# HQspd_board.net
KiCad netlist of a schematic drawn in EAGLE
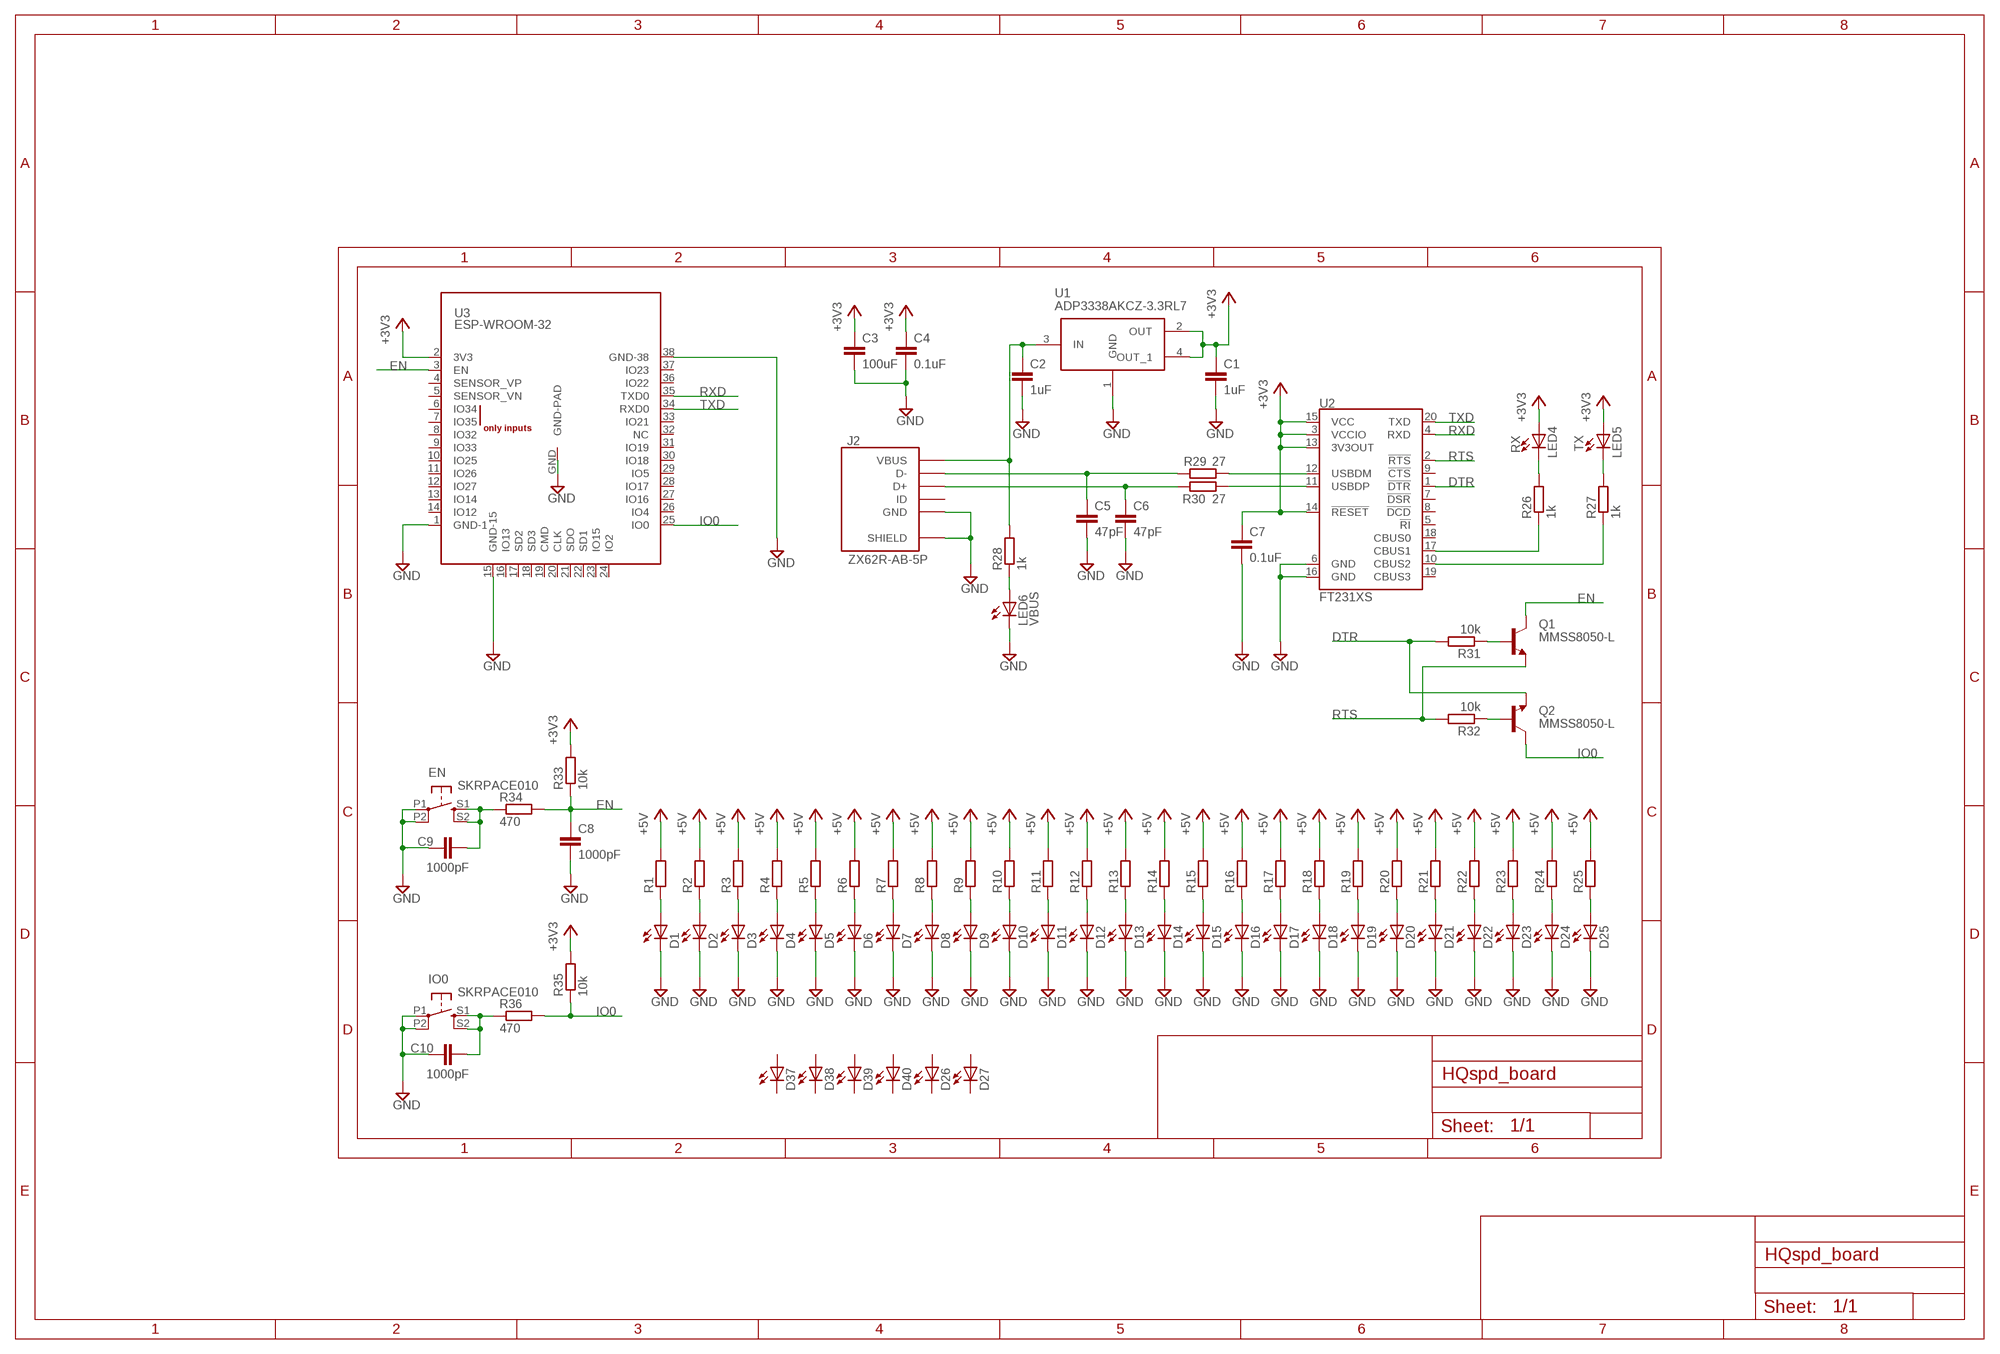
[diagram p0: schematic, sheet 1]

(export (version "E")
  (design (tool "Eeschema 10.0.6"))
  (components
    (comp (ref "C1")
      (value "1uF")
      (footprint "eagle-import:C0603")
      (libsource (lib "eagle-import") (part "C-EUC0603"))
    )
    (comp (ref "C2")
      (value "1uF")
      (footprint "eagle-import:C0603")
      (libsource (lib "eagle-import") (part "C-EUC0603"))
    )
    (comp (ref "C3")
      (value "100uF")
      (footprint "eagle-import:C1210")
      (libsource (lib "eagle-import") (part "C-EUC1210"))
    )
    (comp (ref "C4")
      (value "0.1uF")
      (footprint "eagle-import:C0603")
      (libsource (lib "eagle-import") (part "C-EUC0603"))
    )
    (comp (ref "C5")
      (value "47pF")
      (footprint "eagle-import:C0603")
      (libsource (lib "eagle-import") (part "C-EUC0603"))
    )
    (comp (ref "C6")
      (value "47pF")
      (footprint "eagle-import:C0603")
      (libsource (lib "eagle-import") (part "C-EUC0603"))
    )
    (comp (ref "C7")
      (value "0.1uF")
      (footprint "eagle-import:C0603")
      (libsource (lib "eagle-import") (part "C-EUC0603"))
    )
    (comp (ref "C8")
      (value "1000pF")
      (footprint "eagle-import:C0603")
      (libsource (lib "eagle-import") (part "C-EUC0603"))
    )
    (comp (ref "C9")
      (value "1000pF")
      (footprint "eagle-import:C0603")
      (libsource (lib "eagle-import") (part "C-EUC0603"))
    )
    (comp (ref "C10")
      (value "1000pF")
      (footprint "eagle-import:C0603")
      (libsource (lib "eagle-import") (part "C-EUC0603"))
    )
    (comp (ref "D1")
      (value "LEDCHIPLED_0603")
      (footprint "eagle-import:CHIPLED_0603")
      (libsource (lib "eagle-import") (part "LEDCHIPLED_0603"))
    )
    (comp (ref "D2")
      (value "LEDCHIPLED_0603")
      (footprint "eagle-import:CHIPLED_0603")
      (libsource (lib "eagle-import") (part "LEDCHIPLED_0603"))
    )
    (comp (ref "D3")
      (value "LEDCHIPLED_0603")
      (footprint "eagle-import:CHIPLED_0603")
      (libsource (lib "eagle-import") (part "LEDCHIPLED_0603"))
    )
    (comp (ref "D4")
      (value "LEDCHIPLED_0603")
      (footprint "eagle-import:CHIPLED_0603")
      (libsource (lib "eagle-import") (part "LEDCHIPLED_0603"))
    )
    (comp (ref "D5")
      (value "LEDCHIPLED_0603")
      (footprint "eagle-import:CHIPLED_0603")
      (libsource (lib "eagle-import") (part "LEDCHIPLED_0603"))
    )
    (comp (ref "D6")
      (value "LEDCHIPLED_0603")
      (footprint "eagle-import:CHIPLED_0603")
      (libsource (lib "eagle-import") (part "LEDCHIPLED_0603"))
    )
    (comp (ref "D7")
      (value "LEDCHIPLED_0603")
      (footprint "eagle-import:CHIPLED_0603")
      (libsource (lib "eagle-import") (part "LEDCHIPLED_0603"))
    )
    (comp (ref "D8")
      (value "LEDCHIPLED_0603")
      (footprint "eagle-import:CHIPLED_0603")
      (libsource (lib "eagle-import") (part "LEDCHIPLED_0603"))
    )
    (comp (ref "D9")
      (value "LEDCHIPLED_0603")
      (footprint "eagle-import:CHIPLED_0603")
      (libsource (lib "eagle-import") (part "LEDCHIPLED_0603"))
    )
    (comp (ref "D10")
      (value "LEDCHIPLED_0603")
      (footprint "eagle-import:CHIPLED_0603")
      (libsource (lib "eagle-import") (part "LEDCHIPLED_0603"))
    )
    (comp (ref "D11")
      (value "LEDCHIPLED_0603")
      (footprint "eagle-import:CHIPLED_0603")
      (libsource (lib "eagle-import") (part "LEDCHIPLED_0603"))
    )
    (comp (ref "D12")
      (value "LEDCHIPLED_0603")
      (footprint "eagle-import:CHIPLED_0603")
      (libsource (lib "eagle-import") (part "LEDCHIPLED_0603"))
    )
    (comp (ref "D13")
      (value "LEDCHIPLED_0603")
      (footprint "eagle-import:CHIPLED_0603")
      (libsource (lib "eagle-import") (part "LEDCHIPLED_0603"))
    )
    (comp (ref "D14")
      (value "LEDCHIPLED_0603")
      (footprint "eagle-import:CHIPLED_0603")
      (libsource (lib "eagle-import") (part "LEDCHIPLED_0603"))
    )
    (comp (ref "D15")
      (value "LEDCHIPLED_0603")
      (footprint "eagle-import:CHIPLED_0603")
      (libsource (lib "eagle-import") (part "LEDCHIPLED_0603"))
    )
    (comp (ref "D16")
      (value "LEDCHIPLED_0603")
      (footprint "eagle-import:CHIPLED_0603")
      (libsource (lib "eagle-import") (part "LEDCHIPLED_0603"))
    )
    (comp (ref "D17")
      (value "LEDCHIPLED_0603")
      (footprint "eagle-import:CHIPLED_0603")
      (libsource (lib "eagle-import") (part "LEDCHIPLED_0603"))
    )
    (comp (ref "D18")
      (value "LEDCHIPLED_0603")
      (footprint "eagle-import:CHIPLED_0603")
      (libsource (lib "eagle-import") (part "LEDCHIPLED_0603"))
    )
    (comp (ref "D19")
      (value "LEDCHIPLED_0603")
      (footprint "eagle-import:CHIPLED_0603")
      (libsource (lib "eagle-import") (part "LEDCHIPLED_0603"))
    )
    (comp (ref "D20")
      (value "LEDCHIPLED_0603")
      (footprint "eagle-import:CHIPLED_0603")
      (libsource (lib "eagle-import") (part "LEDCHIPLED_0603"))
    )
    (comp (ref "D21")
      (value "LEDCHIPLED_0603")
      (footprint "eagle-import:CHIPLED_0603")
      (libsource (lib "eagle-import") (part "LEDCHIPLED_0603"))
    )
    (comp (ref "D22")
      (value "LEDCHIPLED_0603")
      (footprint "eagle-import:CHIPLED_0603")
      (libsource (lib "eagle-import") (part "LEDCHIPLED_0603"))
    )
    (comp (ref "D23")
      (value "LEDCHIPLED_0603")
      (footprint "eagle-import:CHIPLED_0603")
      (libsource (lib "eagle-import") (part "LEDCHIPLED_0603"))
    )
    (comp (ref "D24")
      (value "LEDCHIPLED_0603")
      (footprint "eagle-import:CHIPLED_0603")
      (libsource (lib "eagle-import") (part "LEDCHIPLED_0603"))
    )
    (comp (ref "D25")
      (value "LEDCHIPLED_0603")
      (footprint "eagle-import:CHIPLED_0603")
      (libsource (lib "eagle-import") (part "LEDCHIPLED_0603"))
    )
    (comp (ref "D26")
      (value "LED3MM")
      (footprint "eagle-import:LED3MM")
      (libsource (lib "eagle-import") (part "LED3MM"))
    )
    (comp (ref "D27")
      (value "LED3MM")
      (footprint "eagle-import:LED3MM")
      (libsource (lib "eagle-import") (part "LED3MM"))
    )
    (comp (ref "D37")
      (value "LED3MM")
      (footprint "eagle-import:LED3MM")
      (libsource (lib "eagle-import") (part "LED3MM"))
    )
    (comp (ref "D38")
      (value "LED3MM")
      (footprint "eagle-import:LED3MM")
      (libsource (lib "eagle-import") (part "LED3MM"))
    )
    (comp (ref "D39")
      (value "LED3MM")
      (footprint "eagle-import:LED3MM")
      (libsource (lib "eagle-import") (part "LED3MM"))
    )
    (comp (ref "D40")
      (value "LED3MM")
      (footprint "eagle-import:LED3MM")
      (libsource (lib "eagle-import") (part "LED3MM"))
    )
    (comp (ref "EN")
      (value "SKRPACE010")
      (footprint "eagle-import:SKRPACE010")
      (libsource (lib "eagle-import") (part "SKRPACE010"))
    )
    (comp (ref "IO0")
      (value "SKRPACE010")
      (footprint "eagle-import:SKRPACE010")
      (libsource (lib "eagle-import") (part "SKRPACE010"))
    )
    (comp (ref "J2")
      (value "ZX62R-AB-5P")
      (footprint "eagle-import:ZX62R-B-5PA")
      (libsource (lib "eagle-import") (part "ZX62R-AB-5P"))
    )
    (comp (ref "LED4")
      (value "RX")
      (footprint "eagle-import:CHIPLED_0603")
      (libsource (lib "eagle-import") (part "LEDCHIPLED_0603"))
    )
    (comp (ref "LED5")
      (value "TX")
      (footprint "eagle-import:CHIPLED_0603")
      (libsource (lib "eagle-import") (part "LEDCHIPLED_0603"))
    )
    (comp (ref "LED6")
      (value "VBUS")
      (footprint "eagle-import:CHIPLED_0603")
      (libsource (lib "eagle-import") (part "LEDCHIPLED_0603"))
    )
    (comp (ref "Q1")
      (value "MMSS8050-L")
      (footprint "eagle-import:SOT23")
      (libsource (lib "eagle-import") (part "MMSS8050-L"))
    )
    (comp (ref "Q2")
      (value "MMSS8050-L")
      (footprint "eagle-import:SOT23")
      (libsource (lib "eagle-import") (part "MMSS8050-L"))
    )
    (comp (ref "R1")
      (value "R-EU_R0603")
      (footprint "eagle-import:R0603")
      (libsource (lib "eagle-import") (part "R-EU_R0603"))
    )
    (comp (ref "R2")
      (value "R-EU_R0603")
      (footprint "eagle-import:R0603")
      (libsource (lib "eagle-import") (part "R-EU_R0603"))
    )
    (comp (ref "R3")
      (value "R-EU_R0603")
      (footprint "eagle-import:R0603")
      (libsource (lib "eagle-import") (part "R-EU_R0603"))
    )
    (comp (ref "R4")
      (value "R-EU_R0603")
      (footprint "eagle-import:R0603")
      (libsource (lib "eagle-import") (part "R-EU_R0603"))
    )
    (comp (ref "R5")
      (value "R-EU_R0603")
      (footprint "eagle-import:R0603")
      (libsource (lib "eagle-import") (part "R-EU_R0603"))
    )
    (comp (ref "R6")
      (value "R-EU_R0603")
      (footprint "eagle-import:R0603")
      (libsource (lib "eagle-import") (part "R-EU_R0603"))
    )
    (comp (ref "R7")
      (value "R-EU_R0603")
      (footprint "eagle-import:R0603")
      (libsource (lib "eagle-import") (part "R-EU_R0603"))
    )
    (comp (ref "R8")
      (value "R-EU_R0603")
      (footprint "eagle-import:R0603")
      (libsource (lib "eagle-import") (part "R-EU_R0603"))
    )
    (comp (ref "R9")
      (value "R-EU_R0603")
      (footprint "eagle-import:R0603")
      (libsource (lib "eagle-import") (part "R-EU_R0603"))
    )
    (comp (ref "R10")
      (value "R-EU_R0603")
      (footprint "eagle-import:R0603")
      (libsource (lib "eagle-import") (part "R-EU_R0603"))
    )
    (comp (ref "R11")
      (value "R-EU_R0603")
      (footprint "eagle-import:R0603")
      (libsource (lib "eagle-import") (part "R-EU_R0603"))
    )
    (comp (ref "R12")
      (value "R-EU_R0603")
      (footprint "eagle-import:R0603")
      (libsource (lib "eagle-import") (part "R-EU_R0603"))
    )
    (comp (ref "R13")
      (value "R-EU_R0603")
      (footprint "eagle-import:R0603")
      (libsource (lib "eagle-import") (part "R-EU_R0603"))
    )
    (comp (ref "R14")
      (value "R-EU_R0603")
      (footprint "eagle-import:R0603")
      (libsource (lib "eagle-import") (part "R-EU_R0603"))
    )
    (comp (ref "R15")
      (value "R-EU_R0603")
      (footprint "eagle-import:R0603")
      (libsource (lib "eagle-import") (part "R-EU_R0603"))
    )
    (comp (ref "R16")
      (value "R-EU_R0603")
      (footprint "eagle-import:R0603")
      (libsource (lib "eagle-import") (part "R-EU_R0603"))
    )
    (comp (ref "R17")
      (value "R-EU_R0603")
      (footprint "eagle-import:R0603")
      (libsource (lib "eagle-import") (part "R-EU_R0603"))
    )
    (comp (ref "R18")
      (value "R-EU_R0603")
      (footprint "eagle-import:R0603")
      (libsource (lib "eagle-import") (part "R-EU_R0603"))
    )
    (comp (ref "R19")
      (value "R-EU_R0603")
      (footprint "eagle-import:R0603")
      (libsource (lib "eagle-import") (part "R-EU_R0603"))
    )
    (comp (ref "R20")
      (value "R-EU_R0603")
      (footprint "eagle-import:R0603")
      (libsource (lib "eagle-import") (part "R-EU_R0603"))
    )
    (comp (ref "R21")
      (value "R-EU_R0603")
      (footprint "eagle-import:R0603")
      (libsource (lib "eagle-import") (part "R-EU_R0603"))
    )
    (comp (ref "R22")
      (value "R-EU_R0603")
      (footprint "eagle-import:R0603")
      (libsource (lib "eagle-import") (part "R-EU_R0603"))
    )
    (comp (ref "R23")
      (value "R-EU_R0603")
      (footprint "eagle-import:R0603")
      (libsource (lib "eagle-import") (part "R-EU_R0603"))
    )
    (comp (ref "R24")
      (value "R-EU_R0603")
      (footprint "eagle-import:R0603")
      (libsource (lib "eagle-import") (part "R-EU_R0603"))
    )
    (comp (ref "R25")
      (value "R-EU_R0603")
      (footprint "eagle-import:R0603")
      (libsource (lib "eagle-import") (part "R-EU_R0603"))
    )
    (comp (ref "R26")
      (value "1k")
      (footprint "eagle-import:R0603")
      (libsource (lib "eagle-import") (part "R-EU_R0603"))
    )
    (comp (ref "R27")
      (value "1k")
      (footprint "eagle-import:R0603")
      (libsource (lib "eagle-import") (part "R-EU_R0603"))
    )
    (comp (ref "R28")
      (value "1k")
      (footprint "eagle-import:R0603")
      (libsource (lib "eagle-import") (part "R-EU_R0603"))
    )
    (comp (ref "R29")
      (value "27")
      (footprint "eagle-import:R0603")
      (libsource (lib "eagle-import") (part "R-EU_R0603"))
    )
    (comp (ref "R30")
      (value "27")
      (footprint "eagle-import:R0603")
      (libsource (lib "eagle-import") (part "R-EU_R0603"))
    )
    (comp (ref "R31")
      (value "10k")
      (footprint "eagle-import:R0603")
      (libsource (lib "eagle-import") (part "R-EU_R0603"))
    )
    (comp (ref "R32")
      (value "10k")
      (footprint "eagle-import:R0603")
      (libsource (lib "eagle-import") (part "R-EU_R0603"))
    )
    (comp (ref "R33")
      (value "10k")
      (footprint "eagle-import:R0603")
      (libsource (lib "eagle-import") (part "R-EU_R0603"))
    )
    (comp (ref "R34")
      (value "470")
      (footprint "eagle-import:R0603")
      (libsource (lib "eagle-import") (part "R-EU_R0603"))
    )
    (comp (ref "R35")
      (value "10k")
      (footprint "eagle-import:R0603")
      (libsource (lib "eagle-import") (part "R-EU_R0603"))
    )
    (comp (ref "R36")
      (value "470")
      (footprint "eagle-import:R0603")
      (libsource (lib "eagle-import") (part "R-EU_R0603"))
    )
    (comp (ref "U1")
      (value "ADP3338AKCZ-3.3RL7")
      (footprint "eagle-import:SOT230P700X180-4N")
      (fields (field (name "RS_PART_NUMBER") "9126350"))
      (libsource (lib "eagle-import") (part "ADP3338AKCZ-3.3RL7"))
    )
    (comp (ref "U2")
      (value "FT231XS")
      (footprint "eagle-import:SSOP20_L")
      (libsource (lib "eagle-import") (part "FT231XS"))
    )
    (comp (ref "U3")
      (value "ESP-WROOM-32")
      (footprint "eagle-import:ESP-WROOM-32")
      (libsource (lib "eagle-import") (part "ESP-WROOM-32"))
    )
  )
  (nets
    (net (code "1") (name "+3V3") (class "Default")
      (node (ref "C1") (pin "1") (pinfunction "1_1") (pintype "passive"))
      (node (ref "C3") (pin "1") (pinfunction "1_1") (pintype "passive"))
      (node (ref "C4") (pin "1") (pinfunction "1_1") (pintype "passive"))
      (node (ref "C7") (pin "1") (pinfunction "1_1") (pintype "passive"))
      (node (ref "LED4") (pin "A") (pinfunction "A_A") (pintype "passive"))
      (node (ref "LED5") (pin "A") (pinfunction "A_A") (pintype "passive"))
      (node (ref "R33") (pin "2") (pinfunction "2_2") (pintype "passive"))
      (node (ref "R35") (pin "2") (pinfunction "2_2") (pintype "passive"))
      (node (ref "U1") (pin "2") (pinfunction "OUT_2") (pintype "output"))
      (node (ref "U1") (pin "4") (pinfunction "OUT_1_4") (pintype "output"))
      (node (ref "U2") (pin "13") (pinfunction "3V3OUT_13") (pintype "bidirectional"))
      (node (ref "U2") (pin "14") (pinfunction "~{RESET}_14") (pintype "bidirectional"))
      (node (ref "U2") (pin "15") (pinfunction "VCC_15") (pintype "bidirectional"))
      (node (ref "U2") (pin "3") (pinfunction "VCCIO_3") (pintype "bidirectional"))
      (node (ref "U3") (pin "2") (pinfunction "3V3_2") (pintype "bidirectional"))
    )
    (net (code "2") (name "+5V") (class "Default")
      (node (ref "R1") (pin "2") (pinfunction "2_2") (pintype "passive"))
      (node (ref "R10") (pin "2") (pinfunction "2_2") (pintype "passive"))
      (node (ref "R11") (pin "2") (pinfunction "2_2") (pintype "passive"))
      (node (ref "R12") (pin "2") (pinfunction "2_2") (pintype "passive"))
      (node (ref "R13") (pin "2") (pinfunction "2_2") (pintype "passive"))
      (node (ref "R14") (pin "2") (pinfunction "2_2") (pintype "passive"))
      (node (ref "R15") (pin "2") (pinfunction "2_2") (pintype "passive"))
      (node (ref "R16") (pin "2") (pinfunction "2_2") (pintype "passive"))
      (node (ref "R17") (pin "2") (pinfunction "2_2") (pintype "passive"))
      (node (ref "R18") (pin "2") (pinfunction "2_2") (pintype "passive"))
      (node (ref "R19") (pin "2") (pinfunction "2_2") (pintype "passive"))
      (node (ref "R2") (pin "2") (pinfunction "2_2") (pintype "passive"))
      (node (ref "R20") (pin "2") (pinfunction "2_2") (pintype "passive"))
      (node (ref "R21") (pin "2") (pinfunction "2_2") (pintype "passive"))
      (node (ref "R22") (pin "2") (pinfunction "2_2") (pintype "passive"))
      (node (ref "R23") (pin "2") (pinfunction "2_2") (pintype "passive"))
      (node (ref "R24") (pin "2") (pinfunction "2_2") (pintype "passive"))
      (node (ref "R25") (pin "2") (pinfunction "2_2") (pintype "passive"))
      (node (ref "R3") (pin "2") (pinfunction "2_2") (pintype "passive"))
      (node (ref "R4") (pin "2") (pinfunction "2_2") (pintype "passive"))
      (node (ref "R5") (pin "2") (pinfunction "2_2") (pintype "passive"))
      (node (ref "R6") (pin "2") (pinfunction "2_2") (pintype "passive"))
      (node (ref "R7") (pin "2") (pinfunction "2_2") (pintype "passive"))
      (node (ref "R8") (pin "2") (pinfunction "2_2") (pintype "passive"))
      (node (ref "R9") (pin "2") (pinfunction "2_2") (pintype "passive"))
    )
    (net (code "3") (name "/DTR") (class "Default")
      (node (ref "Q2") (pin "E") (pinfunction "E_E") (pintype "passive"))
      (node (ref "R31") (pin "2") (pinfunction "2_2") (pintype "passive"))
      (node (ref "U2") (pin "1") (pinfunction "~{DTR}_1") (pintype "bidirectional"))
    )
    (net (code "4") (name "/EN") (class "Default")
      (node (ref "C8") (pin "1") (pinfunction "1_1") (pintype "passive"))
      (node (ref "Q1") (pin "C") (pinfunction "C_C") (pintype "passive"))
      (node (ref "R33") (pin "1") (pinfunction "1_1") (pintype "passive"))
      (node (ref "R34") (pin "2") (pinfunction "2_2") (pintype "passive"))
      (node (ref "U3") (pin "3") (pinfunction "EN_3") (pintype "bidirectional"))
    )
    (net (code "5") (name "/IO0") (class "Default")
      (node (ref "Q2") (pin "C") (pinfunction "C_C") (pintype "passive"))
      (node (ref "R35") (pin "1") (pinfunction "1_1") (pintype "passive"))
      (node (ref "R36") (pin "2") (pinfunction "2_2") (pintype "passive"))
      (node (ref "U3") (pin "25") (pinfunction "IO0_25") (pintype "bidirectional"))
    )
    (net (code "6") (name "/RTS") (class "Default")
      (node (ref "Q1") (pin "E") (pinfunction "E_E") (pintype "passive"))
      (node (ref "R32") (pin "2") (pinfunction "2_2") (pintype "passive"))
      (node (ref "U2") (pin "2") (pinfunction "~{RTS}_2") (pintype "bidirectional"))
    )
    (net (code "7") (name "/RXD") (class "Default")
      (node (ref "U2") (pin "4") (pinfunction "RXD_4") (pintype "bidirectional"))
      (node (ref "U3") (pin "35") (pinfunction "TXD0_35") (pintype "bidirectional"))
    )
    (net (code "8") (name "/TXD") (class "Default")
      (node (ref "U2") (pin "20") (pinfunction "TXD_20") (pintype "bidirectional"))
      (node (ref "U3") (pin "34") (pinfunction "RXD0_34") (pintype "bidirectional"))
    )
    (net (code "9") (name "GND") (class "Default")
      (node (ref "C1") (pin "2") (pinfunction "2_2") (pintype "passive"))
      (node (ref "C10") (pin "1") (pinfunction "1_1") (pintype "passive"))
      (node (ref "C2") (pin "2") (pinfunction "2_2") (pintype "passive"))
      (node (ref "C3") (pin "2") (pinfunction "2_2") (pintype "passive"))
      (node (ref "C4") (pin "2") (pinfunction "2_2") (pintype "passive"))
      (node (ref "C5") (pin "2") (pinfunction "2_2") (pintype "passive"))
      (node (ref "C6") (pin "2") (pinfunction "2_2") (pintype "passive"))
      (node (ref "C7") (pin "2") (pinfunction "2_2") (pintype "passive"))
      (node (ref "C8") (pin "2") (pinfunction "2_2") (pintype "passive"))
      (node (ref "C9") (pin "1") (pinfunction "1_1") (pintype "passive"))
      (node (ref "D1") (pin "C") (pinfunction "C_C") (pintype "passive"))
      (node (ref "D10") (pin "C") (pinfunction "C_C") (pintype "passive"))
      (node (ref "D11") (pin "C") (pinfunction "C_C") (pintype "passive"))
      (node (ref "D12") (pin "C") (pinfunction "C_C") (pintype "passive"))
      (node (ref "D13") (pin "C") (pinfunction "C_C") (pintype "passive"))
      (node (ref "D14") (pin "C") (pinfunction "C_C") (pintype "passive"))
      (node (ref "D15") (pin "C") (pinfunction "C_C") (pintype "passive"))
      (node (ref "D16") (pin "C") (pinfunction "C_C") (pintype "passive"))
      (node (ref "D17") (pin "C") (pinfunction "C_C") (pintype "passive"))
      (node (ref "D18") (pin "C") (pinfunction "C_C") (pintype "passive"))
      (node (ref "D19") (pin "C") (pinfunction "C_C") (pintype "passive"))
      (node (ref "D2") (pin "C") (pinfunction "C_C") (pintype "passive"))
      (node (ref "D20") (pin "C") (pinfunction "C_C") (pintype "passive"))
      (node (ref "D21") (pin "C") (pinfunction "C_C") (pintype "passive"))
      (node (ref "D22") (pin "C") (pinfunction "C_C") (pintype "passive"))
      (node (ref "D23") (pin "C") (pinfunction "C_C") (pintype "passive"))
      (node (ref "D24") (pin "C") (pinfunction "C_C") (pintype "passive"))
      (node (ref "D25") (pin "C") (pinfunction "C_C") (pintype "passive"))
      (node (ref "D3") (pin "C") (pinfunction "C_C") (pintype "passive"))
      (node (ref "D4") (pin "C") (pinfunction "C_C") (pintype "passive"))
      (node (ref "D5") (pin "C") (pinfunction "C_C") (pintype "passive"))
      (node (ref "D6") (pin "C") (pinfunction "C_C") (pintype "passive"))
      (node (ref "D7") (pin "C") (pinfunction "C_C") (pintype "passive"))
      (node (ref "D8") (pin "C") (pinfunction "C_C") (pintype "passive"))
      (node (ref "D9") (pin "C") (pinfunction "C_C") (pintype "passive"))
      (node (ref "EN") (pin "P1") (pinfunction "P_P1") (pintype "passive"))
      (node (ref "EN") (pin "P2") (pinfunction "P1_P2") (pintype "passive"))
      (node (ref "IO0") (pin "P1") (pinfunction "P_P1") (pintype "passive"))
      (node (ref "IO0") (pin "P2") (pinfunction "P1_P2") (pintype "passive"))
      (node (ref "J2") (pin "GND") (pinfunction "GND_GND") (pintype "bidirectional"))
      (node (ref "J2") (pin "SHIELD@1") (pinfunction "SHIELD_SHIELD@1") (pintype "bidirectional"))
      (node (ref "J2") (pin "SHIELD@2") (pinfunction "SHIELD_SHIELD@2") (pintype "bidirectional"))
      (node (ref "J2") (pin "SHIELD@3") (pinfunction "SHIELD_SHIELD@3") (pintype "bidirectional"))
      (node (ref "J2") (pin "SHIELD@4") (pinfunction "SHIELD_SHIELD@4") (pintype "bidirectional"))
      (node (ref "LED6") (pin "C") (pinfunction "C_C") (pintype "passive"))
      (node (ref "U1") (pin "1") (pinfunction "GND_1") (pintype "power_in"))
      (node (ref "U2") (pin "16") (pinfunction "GND_16") (pintype "bidirectional"))
      (node (ref "U2") (pin "6") (pinfunction "GND_6") (pintype "bidirectional"))
      (node (ref "U3") (pin "1") (pinfunction "GND-1_1") (pintype "bidirectional"))
      (node (ref "U3") (pin "15") (pinfunction "GND-15_15") (pintype "bidirectional"))
      (node (ref "U3") (pin "38") (pinfunction "GND-38_38") (pintype "bidirectional"))
      (node (ref "U3") (pin "GND") (pinfunction "GND-PAD_GND") (pintype "bidirectional"))
    )
    (net (code "10") (name "Net-(C5-Pad1)") (class "Default")
      (node (ref "C5") (pin "1") (pinfunction "1_1") (pintype "passive"))
      (node (ref "J2") (pin "D-") (pinfunction "D-_D-") (pintype "bidirectional"))
      (node (ref "R29") (pin "1") (pinfunction "1_1") (pintype "passive"))
    )
    (net (code "11") (name "Net-(C6-Pad1)") (class "Default")
      (node (ref "C6") (pin "1") (pinfunction "1_1") (pintype "passive"))
      (node (ref "J2") (pin "D+") (pinfunction "D+_D+") (pintype "bidirectional"))
      (node (ref "R30") (pin "1") (pinfunction "1_1") (pintype "passive"))
    )
    (net (code "12") (name "Net-(D1-PadA)") (class "Default")
      (node (ref "D1") (pin "A") (pinfunction "A_A") (pintype "passive"))
      (node (ref "R1") (pin "1") (pinfunction "1_1") (pintype "passive"))
    )
    (net (code "13") (name "Net-(D2-PadA)") (class "Default")
      (node (ref "D2") (pin "A") (pinfunction "A_A") (pintype "passive"))
      (node (ref "R2") (pin "1") (pinfunction "1_1") (pintype "passive"))
    )
    (net (code "14") (name "Net-(D3-PadA)") (class "Default")
      (node (ref "D3") (pin "A") (pinfunction "A_A") (pintype "passive"))
      (node (ref "R3") (pin "1") (pinfunction "1_1") (pintype "passive"))
    )
    (net (code "15") (name "Net-(D4-PadA)") (class "Default")
      (node (ref "D4") (pin "A") (pinfunction "A_A") (pintype "passive"))
      (node (ref "R4") (pin "1") (pinfunction "1_1") (pintype "passive"))
    )
    (net (code "16") (name "Net-(D5-PadA)") (class "Default")
      (node (ref "D5") (pin "A") (pinfunction "A_A") (pintype "passive"))
      (node (ref "R5") (pin "1") (pinfunction "1_1") (pintype "passive"))
    )
    (net (code "17") (name "Net-(D6-PadA)") (class "Default")
      (node (ref "D6") (pin "A") (pinfunction "A_A") (pintype "passive"))
      (node (ref "R6") (pin "1") (pinfunction "1_1") (pintype "passive"))
    )
    (net (code "18") (name "Net-(D7-PadA)") (class "Default")
      (node (ref "D7") (pin "A") (pinfunction "A_A") (pintype "passive"))
      (node (ref "R7") (pin "1") (pinfunction "1_1") (pintype "passive"))
    )
    (net (code "19") (name "Net-(D8-PadA)") (class "Default")
      (node (ref "D8") (pin "A") (pinfunction "A_A") (pintype "passive"))
      (node (ref "R8") (pin "1") (pinfunction "1_1") (pintype "passive"))
    )
    (net (code "20") (name "Net-(D9-PadA)") (class "Default")
      (node (ref "D9") (pin "A") (pinfunction "A_A") (pintype "passive"))
      (node (ref "R9") (pin "1") (pinfunction "1_1") (pintype "passive"))
    )
    (net (code "21") (name "Net-(D10-PadA)") (class "Default")
      (node (ref "D10") (pin "A") (pinfunction "A_A") (pintype "passive"))
      (node (ref "R10") (pin "1") (pinfunction "1_1") (pintype "passive"))
    )
    (net (code "22") (name "Net-(D11-PadA)") (class "Default")
      (node (ref "D11") (pin "A") (pinfunction "A_A") (pintype "passive"))
      (node (ref "R11") (pin "1") (pinfunction "1_1") (pintype "passive"))
    )
    (net (code "23") (name "Net-(D12-PadA)") (class "Default")
      (node (ref "D12") (pin "A") (pinfunction "A_A") (pintype "passive"))
      (node (ref "R12") (pin "1") (pinfunction "1_1") (pintype "passive"))
    )
    (net (code "24") (name "Net-(D13-PadA)") (class "Default")
      (node (ref "D13") (pin "A") (pinfunction "A_A") (pintype "passive"))
      (node (ref "R13") (pin "1") (pinfunction "1_1") (pintype "passive"))
    )
    (net (code "25") (name "Net-(D14-PadA)") (class "Default")
      (node (ref "D14") (pin "A") (pinfunction "A_A") (pintype "passive"))
      (node (ref "R14") (pin "1") (pinfunction "1_1") (pintype "passive"))
    )
    (net (code "26") (name "Net-(D15-PadA)") (class "Default")
      (node (ref "D15") (pin "A") (pinfunction "A_A") (pintype "passive"))
      (node (ref "R15") (pin "1") (pinfunction "1_1") (pintype "passive"))
    )
    (net (code "27") (name "Net-(D16-PadA)") (class "Default")
      (node (ref "D16") (pin "A") (pinfunction "A_A") (pintype "passive"))
      (node (ref "R16") (pin "1") (pinfunction "1_1") (pintype "passive"))
    )
    (net (code "28") (name "Net-(D17-PadA)") (class "Default")
      (node (ref "D17") (pin "A") (pinfunction "A_A") (pintype "passive"))
      (node (ref "R17") (pin "1") (pinfunction "1_1") (pintype "passive"))
    )
    (net (code "29") (name "Net-(D18-PadA)") (class "Default")
      (node (ref "D18") (pin "A") (pinfunction "A_A") (pintype "passive"))
      (node (ref "R18") (pin "1") (pinfunction "1_1") (pintype "passive"))
    )
    (net (code "30") (name "Net-(D19-PadA)") (class "Default")
      (node (ref "D19") (pin "A") (pinfunction "A_A") (pintype "passive"))
      (node (ref "R19") (pin "1") (pinfunction "1_1") (pintype "passive"))
    )
    (net (code "31") (name "Net-(D20-PadA)") (class "Default")
      (node (ref "D20") (pin "A") (pinfunction "A_A") (pintype "passive"))
      (node (ref "R20") (pin "1") (pinfunction "1_1") (pintype "passive"))
    )
    (net (code "32") (name "Net-(D21-PadA)") (class "Default")
      (node (ref "D21") (pin "A") (pinfunction "A_A") (pintype "passive"))
      (node (ref "R21") (pin "1") (pinfunction "1_1") (pintype "passive"))
    )
    (net (code "33") (name "Net-(D22-PadA)") (class "Default")
      (node (ref "D22") (pin "A") (pinfunction "A_A") (pintype "passive"))
      (node (ref "R22") (pin "1") (pinfunction "1_1") (pintype "passive"))
    )
    (net (code "34") (name "Net-(D23-PadA)") (class "Default")
      (node (ref "D23") (pin "A") (pinfunction "A_A") (pintype "passive"))
      (node (ref "R23") (pin "1") (pinfunction "1_1") (pintype "passive"))
    )
    (net (code "35") (name "Net-(D24-PadA)") (class "Default")
      (node (ref "D24") (pin "A") (pinfunction "A_A") (pintype "passive"))
      (node (ref "R24") (pin "1") (pinfunction "1_1") (pintype "passive"))
    )
    (net (code "36") (name "Net-(D25-PadA)") (class "Default")
      (node (ref "D25") (pin "A") (pinfunction "A_A") (pintype "passive"))
      (node (ref "R25") (pin "1") (pinfunction "1_1") (pintype "passive"))
    )
    (net (code "37") (name "Net-(EN-S)") (class "Default")
      (node (ref "C9") (pin "2") (pinfunction "2_2") (pintype "passive"))
      (node (ref "EN") (pin "S1") (pinfunction "S_S1") (pintype "passive"))
      (node (ref "EN") (pin "S2") (pinfunction "S1_S2") (pintype "passive"))
      (node (ref "R34") (pin "1") (pinfunction "1_1") (pintype "passive"))
    )
    (net (code "38") (name "Net-(IO0-S)") (class "Default")
      (node (ref "C10") (pin "2") (pinfunction "2_2") (pintype "passive"))
      (node (ref "IO0") (pin "S1") (pinfunction "S_S1") (pintype "passive"))
      (node (ref "IO0") (pin "S2") (pinfunction "S1_S2") (pintype "passive"))
      (node (ref "R36") (pin "1") (pinfunction "1_1") (pintype "passive"))
    )
    (net (code "39") (name "Net-(J2-VBUS)") (class "Default")
      (node (ref "C2") (pin "1") (pinfunction "1_1") (pintype "passive"))
      (node (ref "J2") (pin "VCC") (pinfunction "VBUS_VCC") (pintype "bidirectional"))
      (node (ref "R28") (pin "2") (pinfunction "2_2") (pintype "passive"))
      (node (ref "U1") (pin "3") (pinfunction "IN_3") (pintype "input"))
    )
    (net (code "40") (name "Net-(LED4-PadC)") (class "Default")
      (node (ref "LED4") (pin "C") (pinfunction "C_C") (pintype "passive"))
      (node (ref "R26") (pin "2") (pinfunction "2_2") (pintype "passive"))
    )
    (net (code "41") (name "Net-(LED5-PadC)") (class "Default")
      (node (ref "LED5") (pin "C") (pinfunction "C_C") (pintype "passive"))
      (node (ref "R27") (pin "2") (pinfunction "2_2") (pintype "passive"))
    )
    (net (code "42") (name "Net-(LED6-PadA)") (class "Default")
      (node (ref "LED6") (pin "A") (pinfunction "A_A") (pintype "passive"))
      (node (ref "R28") (pin "1") (pinfunction "1_1") (pintype "passive"))
    )
    (net (code "43") (name "Net-(Q1-PadB)") (class "Default")
      (node (ref "Q1") (pin "B") (pinfunction "B_B") (pintype "passive"))
      (node (ref "R31") (pin "1") (pinfunction "1_1") (pintype "passive"))
    )
    (net (code "44") (name "Net-(Q2-PadB)") (class "Default")
      (node (ref "Q2") (pin "B") (pinfunction "B_B") (pintype "passive"))
      (node (ref "R32") (pin "1") (pinfunction "1_1") (pintype "passive"))
    )
    (net (code "45") (name "Net-(U2-CBUS1)") (class "Default")
      (node (ref "R26") (pin "1") (pinfunction "1_1") (pintype "passive"))
      (node (ref "U2") (pin "17") (pinfunction "CBUS1_17") (pintype "bidirectional"))
    )
    (net (code "46") (name "Net-(U2-CBUS2)") (class "Default")
      (node (ref "R27") (pin "1") (pinfunction "1_1") (pintype "passive"))
      (node (ref "U2") (pin "10") (pinfunction "CBUS2_10") (pintype "bidirectional"))
    )
    (net (code "47") (name "Net-(U2-USBDM)") (class "Default")
      (node (ref "R29") (pin "2") (pinfunction "2_2") (pintype "passive"))
      (node (ref "U2") (pin "12") (pinfunction "USBDM_12") (pintype "bidirectional"))
    )
    (net (code "48") (name "Net-(U2-USBDP)") (class "Default")
      (node (ref "R30") (pin "2") (pinfunction "2_2") (pintype "passive"))
      (node (ref "U2") (pin "11") (pinfunction "USBDP_11") (pintype "bidirectional"))
    )
    (net (code "49") (name "unconnected-(D26-C-PadK)") (class "Default")
      (node (ref "D26") (pin "K") (pinfunction "C_K") (pintype "passive"))
    )
    (net (code "50") (name "unconnected-(D26-PadA)") (class "Default")
      (node (ref "D26") (pin "A") (pinfunction "A_A") (pintype "passive"))
    )
    (net (code "51") (name "unconnected-(D27-C-PadK)") (class "Default")
      (node (ref "D27") (pin "K") (pinfunction "C_K") (pintype "passive"))
    )
    (net (code "52") (name "unconnected-(D27-PadA)") (class "Default")
      (node (ref "D27") (pin "A") (pinfunction "A_A") (pintype "passive"))
    )
    (net (code "53") (name "unconnected-(D37-C-PadK)") (class "Default")
      (node (ref "D37") (pin "K") (pinfunction "C_K") (pintype "passive"))
    )
    (net (code "54") (name "unconnected-(D37-PadA)") (class "Default")
      (node (ref "D37") (pin "A") (pinfunction "A_A") (pintype "passive"))
    )
    (net (code "55") (name "unconnected-(D38-C-PadK)") (class "Default")
      (node (ref "D38") (pin "K") (pinfunction "C_K") (pintype "passive"))
    )
    (net (code "56") (name "unconnected-(D38-PadA)") (class "Default")
      (node (ref "D38") (pin "A") (pinfunction "A_A") (pintype "passive"))
    )
    (net (code "57") (name "unconnected-(D39-C-PadK)") (class "Default")
      (node (ref "D39") (pin "K") (pinfunction "C_K") (pintype "passive"))
    )
    (net (code "58") (name "unconnected-(D39-PadA)") (class "Default")
      (node (ref "D39") (pin "A") (pinfunction "A_A") (pintype "passive"))
    )
    (net (code "59") (name "unconnected-(D40-C-PadK)") (class "Default")
      (node (ref "D40") (pin "K") (pinfunction "C_K") (pintype "passive"))
    )
    (net (code "60") (name "unconnected-(D40-PadA)") (class "Default")
      (node (ref "D40") (pin "A") (pinfunction "A_A") (pintype "passive"))
    )
    (net (code "61") (name "unconnected-(J2-PadID)") (class "Default")
      (node (ref "J2") (pin "ID") (pinfunction "ID_ID") (pintype "bidirectional"))
    )
    (net (code "62") (name "unconnected-(U2-CBUS0-Pad18)") (class "Default")
      (node (ref "U2") (pin "18") (pinfunction "CBUS0_18") (pintype "bidirectional"))
    )
    (net (code "63") (name "unconnected-(U2-CBUS3-Pad19)") (class "Default")
      (node (ref "U2") (pin "19") (pinfunction "CBUS3_19") (pintype "bidirectional"))
    )
    (net (code "64") (name "unconnected-(U2-~{CTS}-Pad9)") (class "Default")
      (node (ref "U2") (pin "9") (pinfunction "~{CTS}_9") (pintype "bidirectional"))
    )
    (net (code "65") (name "unconnected-(U2-~{DCD}-Pad8)") (class "Default")
      (node (ref "U2") (pin "8") (pinfunction "~{DCD}_8") (pintype "bidirectional"))
    )
    (net (code "66") (name "unconnected-(U2-~{DSR}-Pad7)") (class "Default")
      (node (ref "U2") (pin "7") (pinfunction "~{DSR}_7") (pintype "bidirectional"))
    )
    (net (code "67") (name "unconnected-(U2-~{RI}-Pad5)") (class "Default")
      (node (ref "U2") (pin "5") (pinfunction "~{RI}_5") (pintype "bidirectional"))
    )
    (net (code "68") (name "unconnected-(U3-CLK-Pad20)") (class "Default")
      (node (ref "U3") (pin "20") (pinfunction "CLK_20") (pintype "bidirectional"))
    )
    (net (code "69") (name "unconnected-(U3-CMD-Pad19)") (class "Default")
      (node (ref "U3") (pin "19") (pinfunction "CMD_19") (pintype "bidirectional"))
    )
    (net (code "70") (name "unconnected-(U3-IO2-Pad24)") (class "Default")
      (node (ref "U3") (pin "24") (pinfunction "IO2_24") (pintype "bidirectional"))
    )
    (net (code "71") (name "unconnected-(U3-IO4-Pad26)") (class "Default")
      (node (ref "U3") (pin "26") (pinfunction "IO4_26") (pintype "bidirectional"))
    )
    (net (code "72") (name "unconnected-(U3-IO5-Pad29)") (class "Default")
      (node (ref "U3") (pin "29") (pinfunction "IO5_29") (pintype "bidirectional"))
    )
    (net (code "73") (name "unconnected-(U3-IO12-Pad14)") (class "Default")
      (node (ref "U3") (pin "14") (pinfunction "IO12_14") (pintype "bidirectional"))
    )
    (net (code "74") (name "unconnected-(U3-IO13-Pad16)") (class "Default")
      (node (ref "U3") (pin "16") (pinfunction "IO13_16") (pintype "bidirectional"))
    )
    (net (code "75") (name "unconnected-(U3-IO14-Pad13)") (class "Default")
      (node (ref "U3") (pin "13") (pinfunction "IO14_13") (pintype "bidirectional"))
    )
    (net (code "76") (name "unconnected-(U3-IO15-Pad23)") (class "Default")
      (node (ref "U3") (pin "23") (pinfunction "IO15_23") (pintype "bidirectional"))
    )
    (net (code "77") (name "unconnected-(U3-IO16-Pad27)") (class "Default")
      (node (ref "U3") (pin "27") (pinfunction "IO16_27") (pintype "bidirectional"))
    )
    (net (code "78") (name "unconnected-(U3-IO17-Pad28)") (class "Default")
      (node (ref "U3") (pin "28") (pinfunction "IO17_28") (pintype "bidirectional"))
    )
    (net (code "79") (name "unconnected-(U3-IO18-Pad30)") (class "Default")
      (node (ref "U3") (pin "30") (pinfunction "IO18_30") (pintype "bidirectional"))
    )
    (net (code "80") (name "unconnected-(U3-IO19-Pad31)") (class "Default")
      (node (ref "U3") (pin "31") (pinfunction "IO19_31") (pintype "bidirectional"))
    )
    (net (code "81") (name "unconnected-(U3-IO21-Pad33)") (class "Default")
      (node (ref "U3") (pin "33") (pinfunction "IO21_33") (pintype "bidirectional"))
    )
    (net (code "82") (name "unconnected-(U3-IO22-Pad36)") (class "Default")
      (node (ref "U3") (pin "36") (pinfunction "IO22_36") (pintype "bidirectional"))
    )
    (net (code "83") (name "unconnected-(U3-IO23-Pad37)") (class "Default")
      (node (ref "U3") (pin "37") (pinfunction "IO23_37") (pintype "bidirectional"))
    )
    (net (code "84") (name "unconnected-(U3-IO25-Pad10)") (class "Default")
      (node (ref "U3") (pin "10") (pinfunction "IO25_10") (pintype "bidirectional"))
    )
    (net (code "85") (name "unconnected-(U3-IO26-Pad11)") (class "Default")
      (node (ref "U3") (pin "11") (pinfunction "IO26_11") (pintype "bidirectional"))
    )
    (net (code "86") (name "unconnected-(U3-IO27-Pad12)") (class "Default")
      (node (ref "U3") (pin "12") (pinfunction "IO27_12") (pintype "bidirectional"))
    )
    (net (code "87") (name "unconnected-(U3-IO32-Pad8)") (class "Default")
      (node (ref "U3") (pin "8") (pinfunction "IO32_8") (pintype "bidirectional"))
    )
    (net (code "88") (name "unconnected-(U3-IO33-Pad9)") (class "Default")
      (node (ref "U3") (pin "9") (pinfunction "IO33_9") (pintype "bidirectional"))
    )
    (net (code "89") (name "unconnected-(U3-IO34-Pad6)") (class "Default")
      (node (ref "U3") (pin "6") (pinfunction "IO34_6") (pintype "input"))
    )
    (net (code "90") (name "unconnected-(U3-IO35-Pad7)") (class "Default")
      (node (ref "U3") (pin "7") (pinfunction "IO35_7") (pintype "input"))
    )
    (net (code "91") (name "unconnected-(U3-NC-Pad32)") (class "Default")
      (node (ref "U3") (pin "32") (pinfunction "NC_32") (pintype "bidirectional"))
    )
    (net (code "92") (name "unconnected-(U3-SD1-Pad22)") (class "Default")
      (node (ref "U3") (pin "22") (pinfunction "SD1_22") (pintype "bidirectional"))
    )
    (net (code "93") (name "unconnected-(U3-SD2-Pad17)") (class "Default")
      (node (ref "U3") (pin "17") (pinfunction "SD2_17") (pintype "bidirectional"))
    )
    (net (code "94") (name "unconnected-(U3-SD3-Pad18)") (class "Default")
      (node (ref "U3") (pin "18") (pinfunction "SD3_18") (pintype "bidirectional"))
    )
    (net (code "95") (name "unconnected-(U3-SDO-Pad21)") (class "Default")
      (node (ref "U3") (pin "21") (pinfunction "SDO_21") (pintype "bidirectional"))
    )
    (net (code "96") (name "unconnected-(U3-SENSOR_VN-Pad5)") (class "Default")
      (node (ref "U3") (pin "5") (pinfunction "SENSOR_VN_5") (pintype "input"))
    )
    (net (code "97") (name "unconnected-(U3-SENSOR_VP-Pad4)") (class "Default")
      (node (ref "U3") (pin "4") (pinfunction "SENSOR_VP_4") (pintype "input"))
    )
  )
)
